# PureRingMod-panel.net
KiCad netlist of a schematic drawn in EAGLE
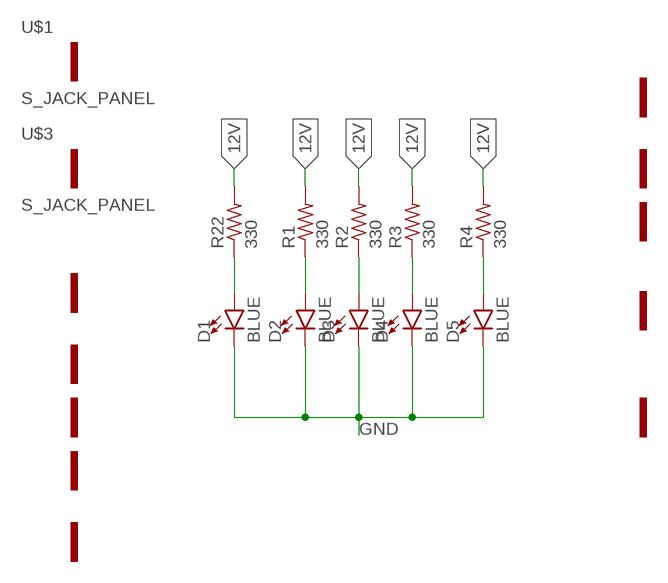
[diagram p0: schematic, sheet 1]
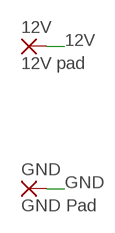
[diagram p1: schematic, sheet 2]

(export (version "E")
  (design (tool "Eeschema 10.0.6"))
  (components
    (comp (ref "D1")
      (value "BLUE")
      (footprint "eagle-import:LED-1206")
      (libsource (lib "eagle-import") (part "LED-BLUE1206"))
    )
    (comp (ref "D2")
      (value "BLUE")
      (footprint "eagle-import:LED-1206")
      (libsource (lib "eagle-import") (part "LED-BLUE1206"))
    )
    (comp (ref "D3")
      (value "BLUE")
      (footprint "eagle-import:LED-1206")
      (libsource (lib "eagle-import") (part "LED-BLUE1206"))
    )
    (comp (ref "D4")
      (value "BLUE")
      (footprint "eagle-import:LED-1206")
      (libsource (lib "eagle-import") (part "LED-BLUE1206"))
    )
    (comp (ref "D5")
      (value "BLUE")
      (footprint "eagle-import:LED-1206")
      (libsource (lib "eagle-import") (part "LED-BLUE1206"))
    )
    (comp (ref "R1")
      (value "330")
      (footprint "eagle-import:R0805")
      (libsource (lib "eagle-import") (part "R-US_R0805"))
    )
    (comp (ref "R2")
      (value "330")
      (footprint "eagle-import:R0805")
      (libsource (lib "eagle-import") (part "R-US_R0805"))
    )
    (comp (ref "R3")
      (value "330")
      (footprint "eagle-import:R0805")
      (libsource (lib "eagle-import") (part "R-US_R0805"))
    )
    (comp (ref "R4")
      (value "330")
      (footprint "eagle-import:R0805")
      (libsource (lib "eagle-import") (part "R-US_R0805"))
    )
    (comp (ref "R22")
      (value "330")
      (footprint "eagle-import:R0805")
      (libsource (lib "eagle-import") (part "R-US_R0805"))
    )
    (comp (ref "U$1")
      (value "S_JACK_PANEL")
      (footprint "eagle-import:S_JACK_PANEL")
      (libsource (lib "eagle-import") (part "S_JACK_PANEL"))
    )
    (comp (ref "U$3")
      (value "S_JACK_PANEL")
      (footprint "eagle-import:S_JACK_PANEL")
      (libsource (lib "eagle-import") (part "S_JACK_PANEL"))
    )
    (comp (ref "U$6")
      (value "POT_PANEL")
      (footprint "eagle-import:POT_PANEL")
      (libsource (lib "eagle-import") (part "POT_PANEL"))
    )
    (comp (ref "U$7")
      (value "POT_PANEL")
      (footprint "eagle-import:POT_PANEL")
      (libsource (lib "eagle-import") (part "POT_PANEL"))
    )
    (comp (ref "U$8")
      (value "POT_PANEL")
      (footprint "eagle-import:POT_PANEL")
      (libsource (lib "eagle-import") (part "POT_PANEL"))
    )
    (comp (ref "U$9")
      (value "POT_PANEL")
      (footprint "eagle-import:POT_PANEL")
      (libsource (lib "eagle-import") (part "POT_PANEL"))
    )
    (comp (ref "U$10")
      (value "POT_PANEL")
      (footprint "eagle-import:POT_PANEL")
      (libsource (lib "eagle-import") (part "POT_PANEL"))
    )
    (comp (ref "U$11")
      (value "XLR_PANEL")
      (footprint "eagle-import:XLR_PANEL")
      (libsource (lib "eagle-import") (part "XLR_PANEL"))
    )
    (comp (ref "U$12")
      (value "MOUNTING_HOLE")
      (footprint "eagle-import:MOUNTING_HOLE")
      (libsource (lib "eagle-import") (part "MOUNTING_HOLE"))
    )
    (comp (ref "U$13")
      (value "MOUNTING_HOLE")
      (footprint "eagle-import:MOUNTING_HOLE")
      (libsource (lib "eagle-import") (part "MOUNTING_HOLE"))
    )
    (comp (ref "U$14")
      (value "MOUNTING_HOLE")
      (footprint "eagle-import:MOUNTING_HOLE")
      (libsource (lib "eagle-import") (part "MOUNTING_HOLE"))
    )
    (comp (ref "U$15")
      (value "MOUNTING_HOLE")
      (footprint "eagle-import:MOUNTING_HOLE")
      (libsource (lib "eagle-import") (part "MOUNTING_HOLE"))
    )
    (comp (ref "12V")
      (value "12V pad")
      (footprint "eagle-import:1,6_0,8")
      (libsource (lib "eagle-import") (part "1,6/0,8"))
    )
    (comp (ref "GND")
      (value "GND Pad")
      (footprint "eagle-import:1,6_0,8")
      (libsource (lib "eagle-import") (part "1,6/0,8"))
    )
  )
  (nets
    (net (code "1") (name "12V") (class "Default")
      (node (ref "12V") (pin "1") (pinfunction "P_1") (pintype "passive"))
      (node (ref "R1") (pin "2") (pinfunction "2_2") (pintype "passive"))
      (node (ref "R2") (pin "2") (pinfunction "2_2") (pintype "passive"))
      (node (ref "R22") (pin "2") (pinfunction "2_2") (pintype "passive"))
      (node (ref "R3") (pin "2") (pinfunction "2_2") (pintype "passive"))
      (node (ref "R4") (pin "2") (pinfunction "2_2") (pintype "passive"))
    )
    (net (code "2") (name "GND") (class "Default")
      (node (ref "D1") (pin "C") (pinfunction "C_C") (pintype "passive"))
      (node (ref "D2") (pin "C") (pinfunction "C_C") (pintype "passive"))
      (node (ref "D3") (pin "C") (pinfunction "C_C") (pintype "passive"))
      (node (ref "D4") (pin "C") (pinfunction "C_C") (pintype "passive"))
      (node (ref "D5") (pin "C") (pinfunction "C_C") (pintype "passive"))
      (node (ref "GND") (pin "1") (pinfunction "P_1") (pintype "passive"))
    )
    (net (code "3") (name "Net-(D1-PadA)") (class "Default")
      (node (ref "D1") (pin "A") (pinfunction "A_A") (pintype "passive"))
      (node (ref "R22") (pin "1") (pinfunction "1_1") (pintype "passive"))
    )
    (net (code "4") (name "Net-(D2-PadA)") (class "Default")
      (node (ref "D2") (pin "A") (pinfunction "A_A") (pintype "passive"))
      (node (ref "R1") (pin "1") (pinfunction "1_1") (pintype "passive"))
    )
    (net (code "5") (name "Net-(D3-PadA)") (class "Default")
      (node (ref "D3") (pin "A") (pinfunction "A_A") (pintype "passive"))
      (node (ref "R2") (pin "1") (pinfunction "1_1") (pintype "passive"))
    )
    (net (code "6") (name "Net-(D4-PadA)") (class "Default")
      (node (ref "D4") (pin "A") (pinfunction "A_A") (pintype "passive"))
      (node (ref "R3") (pin "1") (pinfunction "1_1") (pintype "passive"))
    )
    (net (code "7") (name "Net-(D5-PadA)") (class "Default")
      (node (ref "D5") (pin "A") (pinfunction "A_A") (pintype "passive"))
      (node (ref "R4") (pin "1") (pinfunction "1_1") (pintype "passive"))
    )
  )
)
